# MCU.net
KiCad netlist of a schematic drawn in Altium Designer
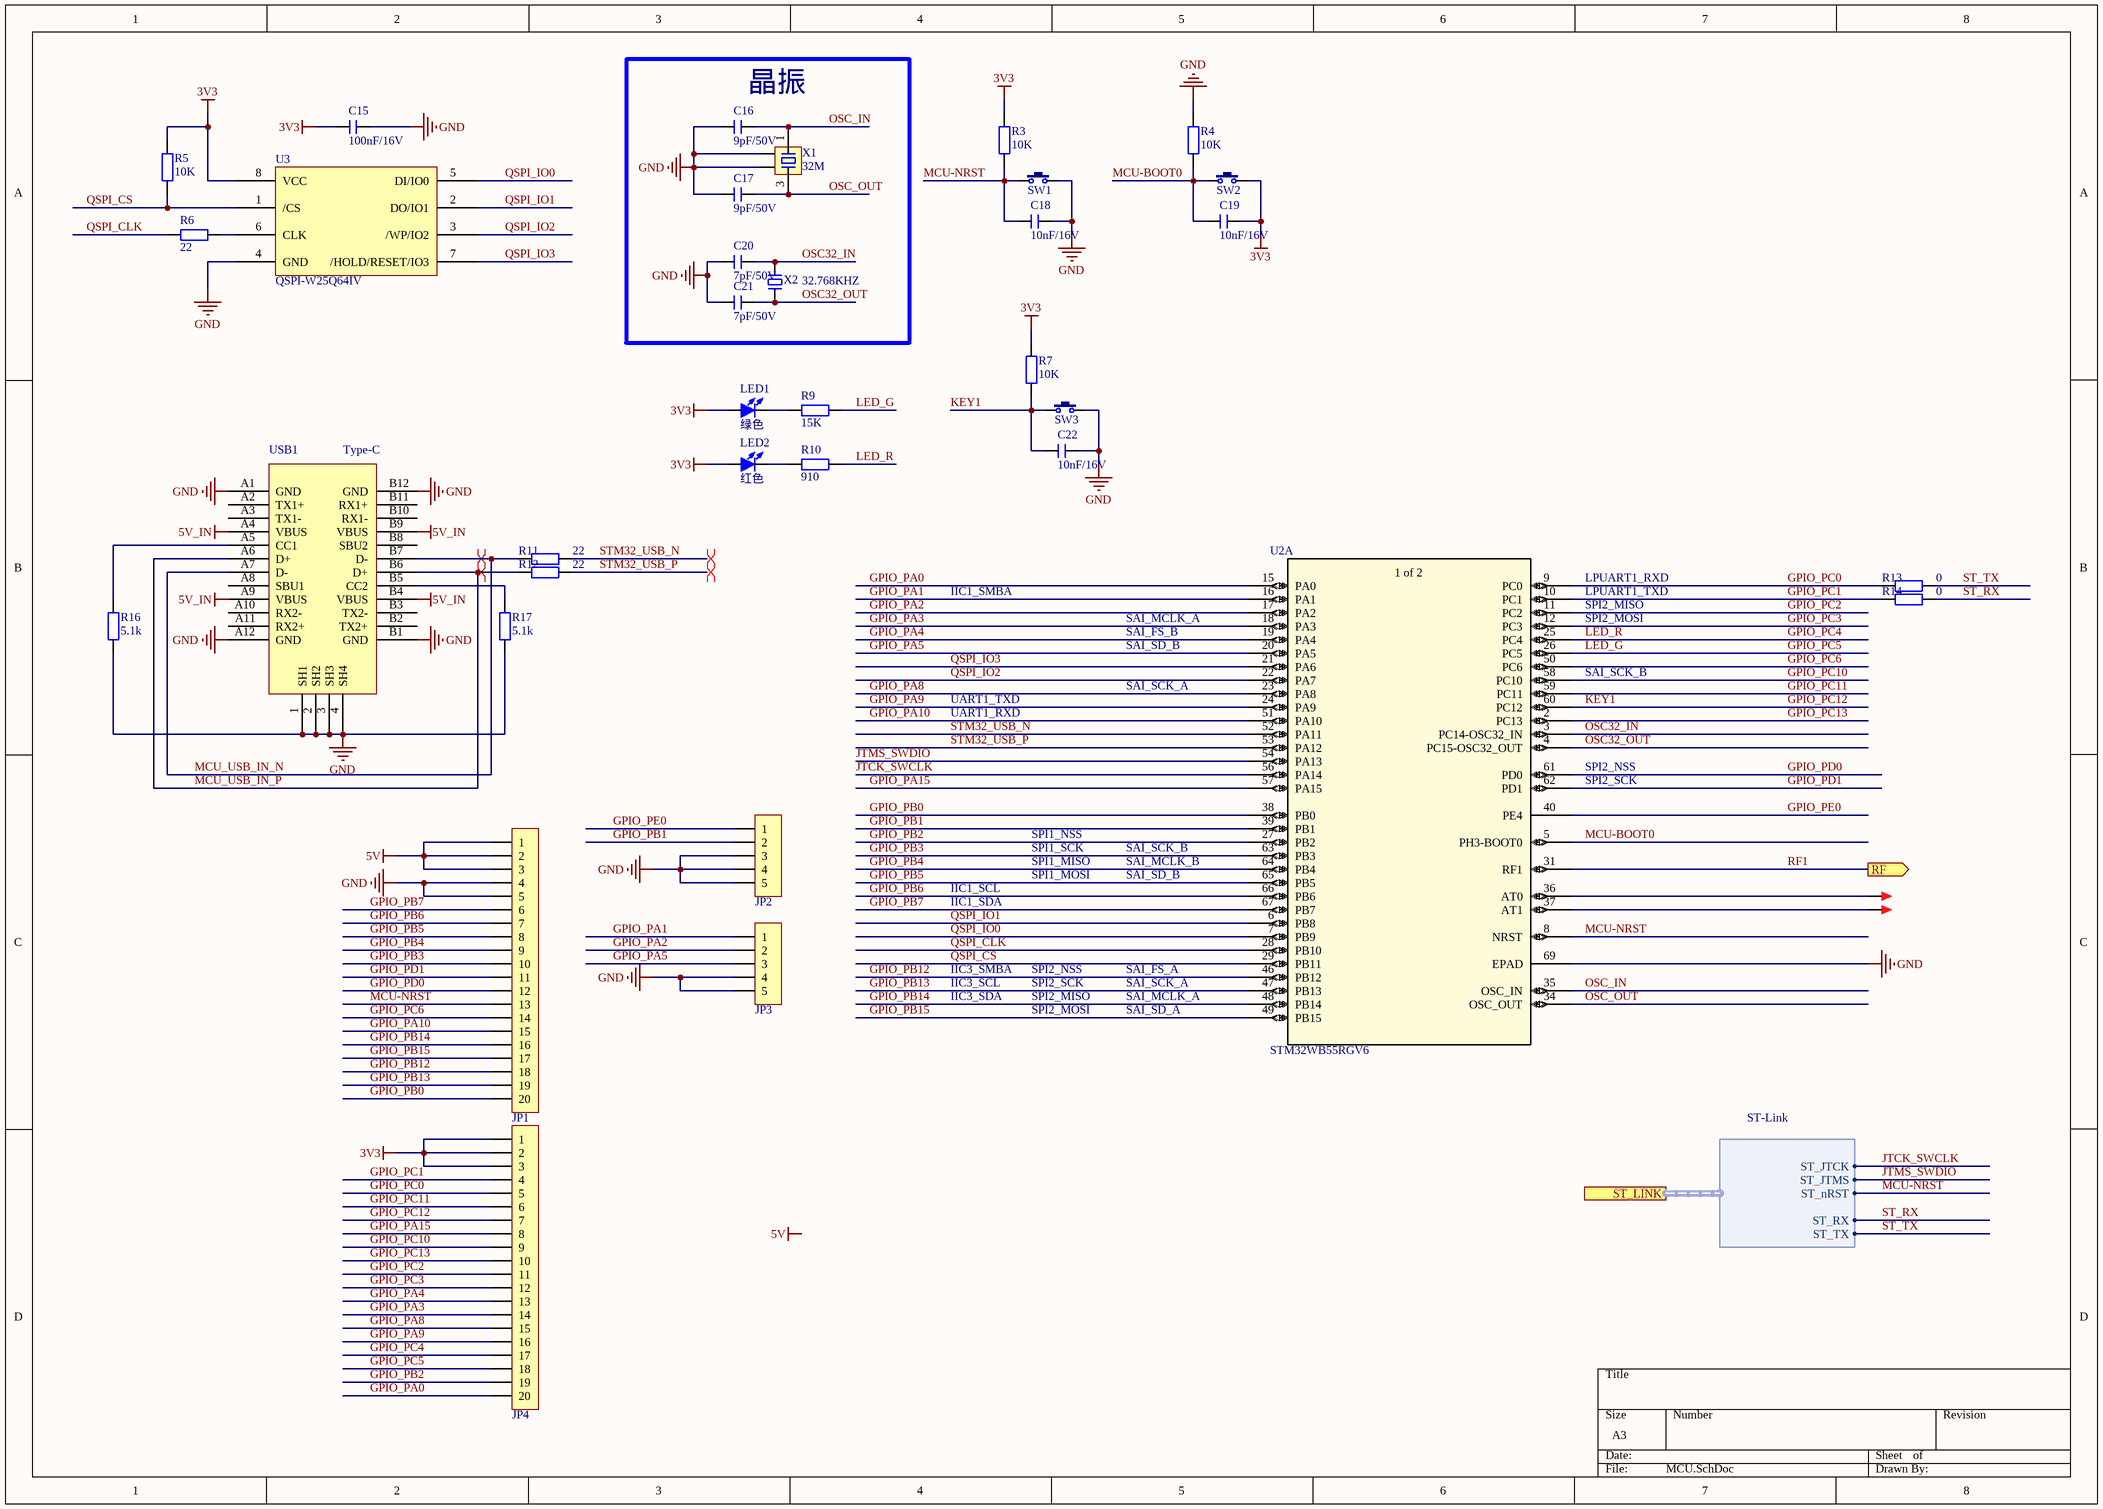
[diagram p0: MCU.SchDoc]

(export (version "E")
  (design (tool "Eeschema 10.0.6"))
  (components
    (comp (ref "C15")
      (value "100nF/16V")
      (footprint "C 0402_L")
      (description "贴片电容")
      (libsource (lib "3.1   - 电阻-电容-电感") (part "C"))
    )
    (comp (ref "C16")
      (value "9pF/50V")
      (footprint "C 0402_L")
      (description "贴片电容")
      (libsource (lib "3.1   - 电阻-电容-电感") (part "C"))
    )
    (comp (ref "C17")
      (value "9pF/50V")
      (footprint "C 0402_L")
      (description "贴片电容")
      (libsource (lib "3.1   - 电阻-电容-电感") (part "C"))
    )
    (comp (ref "C18")
      (value "10nF/16V")
      (footprint "C 0402_L")
      (description "贴片电容")
      (libsource (lib "3.1   - 电阻-电容-电感") (part "C"))
    )
    (comp (ref "C19")
      (value "10nF/16V")
      (footprint "C 0402_L")
      (description "贴片电容")
      (libsource (lib "3.1   - 电阻-电容-电感") (part "C"))
    )
    (comp (ref "C20")
      (value "7pF/50V")
      (footprint "C 0402_L")
      (description "贴片电容")
      (libsource (lib "3.1   - 电阻-电容-电感") (part "C"))
    )
    (comp (ref "C21")
      (value "7pF/50V")
      (footprint "C 0402_L")
      (description "贴片电容")
      (libsource (lib "3.1   - 电阻-电容-电感") (part "C"))
    )
    (comp (ref "C22")
      (value "10nF/16V")
      (footprint "C 0402_L")
      (description "贴片电容")
      (libsource (lib "3.1   - 电阻-电容-电感") (part "C"))
    )
    (comp (ref "JP1")
      (value "HDR-1X20")
      (footprint "HDR2.54-LI-20P")
      (description "20P接插件")
      (libsource (lib "4.5   - 接插件-脚距2.54") (part "Header 20"))
    )
    (comp (ref "JP2")
      (value "HDR-1X5")
      (footprint "HDR2.54-LI-5P")
      (description "5P接插件")
      (libsource (lib "4.5   - 接插件-脚距2.54") (part "Header 5"))
    )
    (comp (ref "JP3")
      (value "HDR-1X5")
      (footprint "HDR2.54-LI-5P")
      (description "5P接插件")
      (libsource (lib "4.5   - 接插件-脚距2.54") (part "Header 5"))
    )
    (comp (ref "JP4")
      (value "HDR-1X20")
      (footprint "HDR2.54-LI-20P")
      (description "20P接插件")
      (libsource (lib "4.5   - 接插件-脚距2.54") (part "Header 20"))
    )
    (comp (ref "LED1")
      (value "绿色")
      (footprint "LED")
      (description "C84267")
      (libsource (lib "9.1   - LED") (part "LED-SMD"))
    )
    (comp (ref "LED2")
      (value "红色")
      (footprint "LED")
      (description "C84267")
      (libsource (lib "9.1   - LED") (part "LED-SMD"))
    )
    (comp (ref "R3")
      (value "10K")
      (footprint "R 0402_L")
      (description "贴片电阻")
      (libsource (lib "3.1   - 电阻-电容-电感") (part "R"))
    )
    (comp (ref "R4")
      (value "10K")
      (footprint "R 0402_L")
      (description "贴片电阻")
      (libsource (lib "3.1   - 电阻-电容-电感") (part "R"))
    )
    (comp (ref "R5")
      (value "10K")
      (footprint "R 0402_L")
      (description "贴片电阻 0402 1%")
      (libsource (lib "3.1   - 电阻-电容-电感") (part "R"))
    )
    (comp (ref "R6")
      (value "22")
      (footprint "R 0402_L")
      (description "贴片电阻 0402 1%")
      (libsource (lib "3.1   - 电阻-电容-电感") (part "R"))
    )
    (comp (ref "R7")
      (value "10K")
      (footprint "R 0402_L")
      (description "贴片电阻")
      (libsource (lib "3.1   - 电阻-电容-电感") (part "R"))
    )
    (comp (ref "R9")
      (value "15K")
      (footprint "R 0402_L")
      (description "贴片电阻 0402 5%")
      (libsource (lib "3.1   - 电阻-电容-电感") (part "R"))
    )
    (comp (ref "R10")
      (value "910")
      (footprint "R 0402_L")
      (description "贴片电阻 0402 5%")
      (libsource (lib "3.1   - 电阻-电容-电感") (part "R"))
    )
    (comp (ref "R11")
      (value "22")
      (footprint "R 0402_L")
      (description "贴片电阻 0402 5%")
      (libsource (lib "3.1   - 电阻-电容-电感") (part "R"))
    )
    (comp (ref "R12")
      (value "22")
      (footprint "R 0402_L")
      (description "贴片电阻 0402 5%")
      (libsource (lib "3.1   - 电阻-电容-电感") (part "R"))
    )
    (comp (ref "R13")
      (value "0")
      (footprint "R 0402_L")
      (description "贴片电阻 0402 5%")
      (libsource (lib "3.1   - 电阻-电容-电感") (part "R"))
    )
    (comp (ref "R14")
      (value "0")
      (footprint "R 0402_L")
      (description "贴片电阻 0402 5%")
      (libsource (lib "3.1   - 电阻-电容-电感") (part "R"))
    )
    (comp (ref "R16")
      (value "5.1k")
      (footprint "R 0402_L")
      (description "贴片电阻 0402 5%")
      (libsource (lib "3.1   - 电阻-电容-电感") (part "R"))
    )
    (comp (ref "R17")
      (value "5.1k")
      (footprint "R 0402_L")
      (description "贴片电阻 0402 5%")
      (libsource (lib "3.1   - 电阻-电容-电感") (part "R"))
    )
    (comp (ref "SW1")
      (value "3x6x5")
      (footprint "按钮")
      (description "3x6轻触开关")
      (libsource (lib "5.1   - 按键-开关") (part "TSW 3x6"))
    )
    (comp (ref "SW2")
      (value "3x6x5")
      (footprint "按钮")
      (description "3x6轻触开关")
      (libsource (lib "5.1   - 按键-开关") (part "TSW 3x6"))
    )
    (comp (ref "SW3")
      (value "3x6x5")
      (footprint "按钮")
      (description "3x6轻触开关")
      (libsource (lib "5.1   - 按键-开关") (part "TSW 3x6"))
    )
    (comp (ref "TP1")
      (value "TEST")
      (footprint "TEST 1.2")
      (description "测试点")
      (libsource (lib "15.1 - 未分类器件") (part "TEST"))
    )
    (comp (ref "TP2")
      (value "TEST")
      (footprint "TEST 1.2")
      (description "测试点")
      (libsource (lib "15.1 - 未分类器件") (part "TEST"))
    )
    (comp (ref "U2")
      (value "STM32WB55RGV6")
      (footprint "VFQFN68-8x8mm-M")
      (description "No Description Available")
      (fields (field (name "COPYRIGHT") "Copyright (C) 2018 Accelerated Designs. All rights reserved"))
      (libsource (lib "2021-04-01_09-06-49") (part "STM32WB55RGV6"))
    )
    (comp (ref "U3")
      (value "QSPI-W25Q64IV")
      (footprint "QSPI")
      (libsource (lib "AltiumV15") (part "QSPI-W25Q256IV"))
    )
    (comp (ref "USB1")
      (value "Type-C")
      (footprint "Type-c接口")
      (libsource (lib "MyPcbLib") (part "USB-Type-C-TOP"))
    )
    (comp (ref "X1")
      (value "32M")
      (footprint "OSC 1612-4P")
      (description "4脚无源晶振")
      (libsource (lib "10.1 - 保险丝-晶振") (part "XTAL-4P"))
    )
    (comp (ref "X2")
      (value "32.768KHZ")
      (footprint "OSC 3215-2P")
      (description "2脚无源脚晶振")
      (libsource (lib "10.1 - 保险丝-晶振") (part "XTAL-2P"))
    )
  )
  (nets
    (net (code "2") (name "/GPIO_PA0") (class "Default")
      (node (ref "JP4") (pin "20") (pinfunction "20_20") (pintype "passive"))
      (node (ref "U2") (pin "15") (pinfunction "PA0_15") (pintype "bidirectional"))
    )
    (net (code "3") (name "/GPIO_PA1") (class "Default")
      (node (ref "JP3") (pin "1") (pinfunction "1_1") (pintype "passive"))
      (node (ref "U2") (pin "16") (pinfunction "PA1_16") (pintype "bidirectional"))
    )
    (net (code "4") (name "/GPIO_PA2") (class "Default")
      (node (ref "JP3") (pin "2") (pinfunction "2_2") (pintype "passive"))
      (node (ref "U2") (pin "17") (pinfunction "PA2_17") (pintype "bidirectional"))
    )
    (net (code "5") (name "/GPIO_PA3") (class "Default")
      (node (ref "JP4") (pin "14") (pinfunction "14_14") (pintype "passive"))
      (node (ref "U2") (pin "18") (pinfunction "PA3_18") (pintype "bidirectional"))
    )
    (net (code "6") (name "/GPIO_PA4") (class "Default")
      (node (ref "JP4") (pin "13") (pinfunction "13_13") (pintype "passive"))
      (node (ref "U2") (pin "19") (pinfunction "PA4_19") (pintype "bidirectional"))
    )
    (net (code "7") (name "/GPIO_PA5") (class "Default")
      (node (ref "JP3") (pin "3") (pinfunction "3_3") (pintype "passive"))
      (node (ref "U2") (pin "20") (pinfunction "PA5_20") (pintype "bidirectional"))
    )
    (net (code "8") (name "/GPIO_PA8") (class "Default")
      (node (ref "JP4") (pin "15") (pinfunction "15_15") (pintype "passive"))
      (node (ref "U2") (pin "23") (pinfunction "PA8_23") (pintype "bidirectional"))
    )
    (net (code "9") (name "/GPIO_PA9") (class "Default")
      (node (ref "JP4") (pin "16") (pinfunction "16_16") (pintype "passive"))
      (node (ref "U2") (pin "24") (pinfunction "PA9_24") (pintype "bidirectional"))
    )
    (net (code "10") (name "/GPIO_PA10") (class "Default")
      (node (ref "JP1") (pin "15") (pinfunction "15_15") (pintype "passive"))
      (node (ref "U2") (pin "51") (pinfunction "PA10_51") (pintype "bidirectional"))
    )
    (net (code "11") (name "/GPIO_PA15") (class "Default")
      (node (ref "JP4") (pin "8") (pinfunction "8_8") (pintype "passive"))
      (node (ref "U2") (pin "57") (pinfunction "PA15_57") (pintype "bidirectional"))
    )
    (net (code "12") (name "/GPIO_PB0") (class "Default")
      (node (ref "JP1") (pin "20") (pinfunction "20_20") (pintype "passive"))
      (node (ref "U2") (pin "38") (pinfunction "PB0_38") (pintype "bidirectional"))
    )
    (net (code "13") (name "/GPIO_PB1") (class "Default")
      (node (ref "JP2") (pin "2") (pinfunction "2_2") (pintype "passive"))
      (node (ref "U2") (pin "39") (pinfunction "PB1_39") (pintype "bidirectional"))
    )
    (net (code "14") (name "/GPIO_PB2") (class "Default")
      (node (ref "JP4") (pin "19") (pinfunction "19_19") (pintype "passive"))
      (node (ref "U2") (pin "27") (pinfunction "PB2_27") (pintype "bidirectional"))
    )
    (net (code "15") (name "/GPIO_PB3") (class "Default")
      (node (ref "JP1") (pin "10") (pinfunction "10_10") (pintype "passive"))
      (node (ref "U2") (pin "63") (pinfunction "PB3_63") (pintype "bidirectional"))
    )
    (net (code "16") (name "/GPIO_PB4") (class "Default")
      (node (ref "JP1") (pin "9") (pinfunction "9_9") (pintype "passive"))
      (node (ref "U2") (pin "64") (pinfunction "PB4_64") (pintype "bidirectional"))
    )
    (net (code "17") (name "/GPIO_PB5") (class "Default")
      (node (ref "JP1") (pin "8") (pinfunction "8_8") (pintype "passive"))
      (node (ref "U2") (pin "65") (pinfunction "PB5_65") (pintype "bidirectional"))
    )
    (net (code "18") (name "/GPIO_PB6") (class "Default")
      (node (ref "JP1") (pin "7") (pinfunction "7_7") (pintype "passive"))
      (node (ref "U2") (pin "66") (pinfunction "PB6_66") (pintype "bidirectional"))
    )
    (net (code "19") (name "/GPIO_PB7") (class "Default")
      (node (ref "JP1") (pin "6") (pinfunction "6_6") (pintype "passive"))
      (node (ref "U2") (pin "67") (pinfunction "PB7_67") (pintype "bidirectional"))
    )
    (net (code "20") (name "/GPIO_PB12") (class "Default")
      (node (ref "JP1") (pin "18") (pinfunction "18_18") (pintype "passive"))
      (node (ref "U2") (pin "46") (pinfunction "PB12_46") (pintype "bidirectional"))
    )
    (net (code "21") (name "/GPIO_PB13") (class "Default")
      (node (ref "JP1") (pin "19") (pinfunction "19_19") (pintype "passive"))
      (node (ref "U2") (pin "47") (pinfunction "PB13_47") (pintype "bidirectional"))
    )
    (net (code "22") (name "/GPIO_PB14") (class "Default")
      (node (ref "JP1") (pin "16") (pinfunction "16_16") (pintype "passive"))
      (node (ref "U2") (pin "48") (pinfunction "PB14_48") (pintype "bidirectional"))
    )
    (net (code "23") (name "/GPIO_PB15") (class "Default")
      (node (ref "JP1") (pin "17") (pinfunction "17_17") (pintype "passive"))
      (node (ref "U2") (pin "49") (pinfunction "PB15_49") (pintype "bidirectional"))
    )
    (net (code "24") (name "/GPIO_PC0") (class "Default")
      (node (ref "JP4") (pin "5") (pinfunction "5_5") (pintype "passive"))
      (node (ref "R13") (pin "2") (pinfunction "2_2") (pintype "passive"))
      (node (ref "U2") (pin "9") (pinfunction "PC0_9") (pintype "bidirectional"))
    )
    (net (code "25") (name "/GPIO_PC1") (class "Default")
      (node (ref "JP4") (pin "4") (pinfunction "4_4") (pintype "passive"))
      (node (ref "R14") (pin "2") (pinfunction "2_2") (pintype "passive"))
      (node (ref "U2") (pin "10") (pinfunction "PC1_10") (pintype "bidirectional"))
    )
    (net (code "26") (name "/GPIO_PC2") (class "Default")
      (node (ref "JP4") (pin "11") (pinfunction "11_11") (pintype "passive"))
      (node (ref "U2") (pin "11") (pinfunction "PC2_11") (pintype "bidirectional"))
    )
    (net (code "27") (name "/GPIO_PC3") (class "Default")
      (node (ref "JP4") (pin "12") (pinfunction "12_12") (pintype "passive"))
      (node (ref "U2") (pin "12") (pinfunction "PC3_12") (pintype "bidirectional"))
    )
    (net (code "28") (name "/GPIO_PC4") (class "Default")
      (node (ref "JP4") (pin "17") (pinfunction "17_17") (pintype "passive"))
      (node (ref "R10") (pin "1") (pinfunction "1_1") (pintype "passive"))
      (node (ref "U2") (pin "25") (pinfunction "PC4_25") (pintype "bidirectional"))
    )
    (net (code "29") (name "/GPIO_PC5") (class "Default")
      (node (ref "JP4") (pin "18") (pinfunction "18_18") (pintype "passive"))
      (node (ref "R9") (pin "1") (pinfunction "1_1") (pintype "passive"))
      (node (ref "U2") (pin "26") (pinfunction "PC5_26") (pintype "bidirectional"))
    )
    (net (code "30") (name "/GPIO_PC6") (class "Default")
      (node (ref "JP1") (pin "14") (pinfunction "14_14") (pintype "passive"))
      (node (ref "U2") (pin "50") (pinfunction "PC6_50") (pintype "bidirectional"))
    )
    (net (code "31") (name "/GPIO_PC10") (class "Default")
      (node (ref "JP4") (pin "9") (pinfunction "9_9") (pintype "passive"))
      (node (ref "U2") (pin "58") (pinfunction "PC10_58") (pintype "bidirectional"))
    )
    (net (code "32") (name "/GPIO_PC11") (class "Default")
      (node (ref "JP4") (pin "6") (pinfunction "6_6") (pintype "passive"))
      (node (ref "U2") (pin "59") (pinfunction "PC11_59") (pintype "bidirectional"))
    )
    (net (code "33") (name "/GPIO_PC12") (class "Default")
      (node (ref "C22") (pin "1") (pinfunction "1_1") (pintype "passive"))
      (node (ref "JP4") (pin "7") (pinfunction "7_7") (pintype "passive"))
      (node (ref "R7") (pin "1") (pinfunction "1_1") (pintype "passive"))
      (node (ref "SW3") (pin "1") (pinfunction "1_1") (pintype "passive"))
      (node (ref "U2") (pin "60") (pinfunction "PC12_60") (pintype "bidirectional"))
    )
    (net (code "34") (name "/GPIO_PC13") (class "Default")
      (node (ref "JP4") (pin "10") (pinfunction "10_10") (pintype "passive"))
      (node (ref "U2") (pin "2") (pinfunction "PC13_2") (pintype "bidirectional"))
    )
    (net (code "35") (name "/GPIO_PD0") (class "Default")
      (node (ref "JP1") (pin "12") (pinfunction "12_12") (pintype "passive"))
      (node (ref "U2") (pin "61") (pinfunction "PD0_61") (pintype "bidirectional"))
    )
    (net (code "36") (name "/GPIO_PD1") (class "Default")
      (node (ref "JP1") (pin "11") (pinfunction "11_11") (pintype "passive"))
      (node (ref "U2") (pin "62") (pinfunction "PD1_62") (pintype "bidirectional"))
    )
    (net (code "37") (name "/GPIO_PE0") (class "Default")
      (node (ref "JP2") (pin "1") (pinfunction "1_1") (pintype "passive"))
      (node (ref "U2") (pin "40") (pinfunction "PE4_40") (pintype "power_in"))
    )
    (net (code "38") (name "/JTCK_SWCLK") (class "Default")
      (node (ref "U2") (pin "56") (pinfunction "PA14_56") (pintype "bidirectional"))
    )
    (net (code "39") (name "/JTMS_SWDIO") (class "Default")
      (node (ref "U2") (pin "54") (pinfunction "PA13_54") (pintype "bidirectional"))
    )
    (net (code "40") (name "/MCU-BOOT0") (class "Default")
      (node (ref "C19") (pin "1") (pinfunction "1_1") (pintype "passive"))
      (node (ref "R4") (pin "1") (pinfunction "1_1") (pintype "passive"))
      (node (ref "SW2") (pin "1") (pinfunction "1_1") (pintype "passive"))
      (node (ref "U2") (pin "5") (pinfunction "PH3-BOOT0_5") (pintype "bidirectional"))
    )
    (net (code "41") (name "/MCU-NRST") (class "Default")
      (node (ref "C18") (pin "1") (pinfunction "1_1") (pintype "passive"))
      (node (ref "JP1") (pin "13") (pinfunction "13_13") (pintype "passive"))
      (node (ref "R3") (pin "1") (pinfunction "1_1") (pintype "passive"))
      (node (ref "SW1") (pin "1") (pinfunction "1_1") (pintype "passive"))
      (node (ref "U2") (pin "8") (pinfunction "NRST_8") (pintype "bidirectional"))
    )
    (net (code "42") (name "/MCU_USB_IN_N") (class "Default")
      (node (ref "R11") (pin "2") (pinfunction "2_2") (pintype "passive"))
      (node (ref "USB1") (pin "A7") (pinfunction "D-_A7") (pintype "passive"))
      (node (ref "USB1") (pin "B7") (pinfunction "D-_B7") (pintype "passive"))
    )
    (net (code "43") (name "/MCU_USB_IN_P") (class "Default")
      (node (ref "R12") (pin "2") (pinfunction "2_2") (pintype "passive"))
      (node (ref "USB1") (pin "A6") (pinfunction "D+_A6") (pintype "passive"))
      (node (ref "USB1") (pin "B6") (pinfunction "D+_B6") (pintype "passive"))
    )
    (net (code "44") (name "/OSC32_IN") (class "Default")
      (node (ref "C20") (pin "2") (pinfunction "2_2") (pintype "passive"))
      (node (ref "U2") (pin "3") (pinfunction "PC14-OSC32_IN_3") (pintype "bidirectional"))
      (node (ref "X2") (pin "2") (pinfunction "2_2") (pintype "passive"))
    )
    (net (code "45") (name "/OSC32_OUT") (class "Default")
      (node (ref "C21") (pin "2") (pinfunction "2_2") (pintype "passive"))
      (node (ref "U2") (pin "4") (pinfunction "PC15-OSC32_OUT_4") (pintype "bidirectional"))
      (node (ref "X2") (pin "1") (pinfunction "1_1") (pintype "passive"))
    )
    (net (code "46") (name "/OSC_IN") (class "Default")
      (node (ref "C16") (pin "2") (pinfunction "2_2") (pintype "passive"))
      (node (ref "U2") (pin "35") (pinfunction "OSC_IN_35") (pintype "bidirectional"))
      (node (ref "X1") (pin "1") (pinfunction "1_1") (pintype "passive"))
    )
    (net (code "47") (name "/OSC_OUT") (class "Default")
      (node (ref "C17") (pin "2") (pinfunction "2_2") (pintype "passive"))
      (node (ref "U2") (pin "34") (pinfunction "OSC_OUT_34") (pintype "bidirectional"))
      (node (ref "X1") (pin "3") (pinfunction "3_3") (pintype "passive"))
    )
    (net (code "48") (name "/QSPI_CLK") (class "Default")
      (node (ref "R6") (pin "1") (pinfunction "1_1") (pintype "passive"))
      (node (ref "U2") (pin "28") (pinfunction "PB10_28") (pintype "bidirectional"))
    )
    (net (code "49") (name "/QSPI_CS") (class "Default")
      (node (ref "R5") (pin "2") (pinfunction "2_2") (pintype "passive"))
      (node (ref "U2") (pin "29") (pinfunction "PB11_29") (pintype "bidirectional"))
      (node (ref "U3") (pin "1") (pinfunction "/CS_1") (pintype "passive"))
    )
    (net (code "50") (name "/QSPI_IO0") (class "Default")
      (node (ref "U2") (pin "7") (pinfunction "PB9_7") (pintype "bidirectional"))
      (node (ref "U3") (pin "5") (pinfunction "DI/IO0_5") (pintype "passive"))
    )
    (net (code "51") (name "/QSPI_IO1") (class "Default")
      (node (ref "U2") (pin "6") (pinfunction "PB8_6") (pintype "bidirectional"))
      (node (ref "U3") (pin "2") (pinfunction "DO/IO1_2") (pintype "passive"))
    )
    (net (code "52") (name "/QSPI_IO2") (class "Default")
      (node (ref "U2") (pin "22") (pinfunction "PA7_22") (pintype "bidirectional"))
      (node (ref "U3") (pin "3") (pinfunction "/WP/IO2_3") (pintype "passive"))
    )
    (net (code "53") (name "/QSPI_IO3") (class "Default")
      (node (ref "U2") (pin "21") (pinfunction "PA6_21") (pintype "bidirectional"))
      (node (ref "U3") (pin "7") (pinfunction "/HOLD/RESET/IO3_7") (pintype "passive"))
    )
    (net (code "54") (name "/RF1") (class "Default")
      (node (ref "U2") (pin "31") (pinfunction "RF1_31") (pintype "bidirectional"))
    )
    (net (code "55") (name "/STM32_USB_N") (class "Default")
      (node (ref "R11") (pin "1") (pinfunction "1_1") (pintype "passive"))
      (node (ref "U2") (pin "52") (pinfunction "PA11_52") (pintype "bidirectional"))
    )
    (net (code "56") (name "/STM32_USB_P") (class "Default")
      (node (ref "R12") (pin "1") (pinfunction "1_1") (pintype "passive"))
      (node (ref "U2") (pin "53") (pinfunction "PA12_53") (pintype "bidirectional"))
    )
    (net (code "57") (name "/ST_RX") (class "Default")
      (node (ref "R14") (pin "1") (pinfunction "1_1") (pintype "passive"))
    )
    (net (code "58") (name "/ST_TX") (class "Default")
      (node (ref "R13") (pin "1") (pinfunction "1_1") (pintype "passive"))
    )
    (net (code "60") (name "3V3") (class "Default")
      (node (ref "C15") (pin "2") (pinfunction "2_2") (pintype "passive"))
      (node (ref "C19") (pin "2") (pinfunction "2_2") (pintype "passive"))
      (node (ref "JP4") (pin "1") (pinfunction "1_1") (pintype "passive"))
      (node (ref "JP4") (pin "2") (pinfunction "2_2") (pintype "passive"))
      (node (ref "JP4") (pin "3") (pinfunction "3_3") (pintype "passive"))
      (node (ref "LED1") (pin "1") (pinfunction "A_1") (pintype "passive"))
      (node (ref "LED2") (pin "1") (pinfunction "A_1") (pintype "passive"))
      (node (ref "R3") (pin "2") (pinfunction "2_2") (pintype "passive"))
      (node (ref "R5") (pin "1") (pinfunction "1_1") (pintype "passive"))
      (node (ref "R7") (pin "2") (pinfunction "2_2") (pintype "passive"))
      (node (ref "SW2") (pin "2") (pinfunction "2_2") (pintype "passive"))
      (node (ref "U3") (pin "8") (pinfunction "VCC_8") (pintype "passive"))
    )
    (net (code "61") (name "5V") (class "Default")
      (node (ref "JP1") (pin "1") (pinfunction "1_1") (pintype "passive"))
      (node (ref "JP1") (pin "2") (pinfunction "2_2") (pintype "passive"))
      (node (ref "JP1") (pin "3") (pinfunction "3_3") (pintype "passive"))
    )
    (net (code "62") (name "5V_IN") (class "Default")
      (node (ref "USB1") (pin "A4") (pinfunction "VBUS_A4") (pintype "passive"))
      (node (ref "USB1") (pin "A9") (pinfunction "VBUS_A9") (pintype "passive"))
      (node (ref "USB1") (pin "B4") (pinfunction "VBUS_B4") (pintype "passive"))
      (node (ref "USB1") (pin "B9") (pinfunction "VBUS_B9") (pintype "passive"))
    )
    (net (code "63") (name "GND") (class "Default")
      (node (ref "C15") (pin "1") (pinfunction "1_1") (pintype "passive"))
      (node (ref "C16") (pin "1") (pinfunction "1_1") (pintype "passive"))
      (node (ref "C17") (pin "1") (pinfunction "1_1") (pintype "passive"))
      (node (ref "C18") (pin "2") (pinfunction "2_2") (pintype "passive"))
      (node (ref "C20") (pin "1") (pinfunction "1_1") (pintype "passive"))
      (node (ref "C21") (pin "1") (pinfunction "1_1") (pintype "passive"))
      (node (ref "C22") (pin "2") (pinfunction "2_2") (pintype "passive"))
      (node (ref "JP1") (pin "4") (pinfunction "4_4") (pintype "passive"))
      (node (ref "JP1") (pin "5") (pinfunction "5_5") (pintype "passive"))
      (node (ref "JP2") (pin "3") (pinfunction "3_3") (pintype "passive"))
      (node (ref "JP2") (pin "4") (pinfunction "4_4") (pintype "passive"))
      (node (ref "JP2") (pin "5") (pinfunction "5_5") (pintype "passive"))
      (node (ref "JP3") (pin "4") (pinfunction "4_4") (pintype "passive"))
      (node (ref "JP3") (pin "5") (pinfunction "5_5") (pintype "passive"))
      (node (ref "R16") (pin "2") (pinfunction "2_2") (pintype "passive"))
      (node (ref "R17") (pin "2") (pinfunction "2_2") (pintype "passive"))
      (node (ref "R4") (pin "2") (pinfunction "2_2") (pintype "passive"))
      (node (ref "SW1") (pin "2") (pinfunction "2_2") (pintype "passive"))
      (node (ref "SW3") (pin "2") (pinfunction "2_2") (pintype "passive"))
      (node (ref "U2") (pin "69") (pinfunction "EPAD_69") (pintype "passive"))
      (node (ref "U3") (pin "4") (pinfunction "GND_4") (pintype "passive"))
      (node (ref "USB1") (pin "1") (pinfunction "SH1_1") (pintype "passive"))
      (node (ref "USB1") (pin "2") (pinfunction "SH2_2") (pintype "passive"))
      (node (ref "USB1") (pin "3") (pinfunction "SH3_3") (pintype "passive"))
      (node (ref "USB1") (pin "4") (pinfunction "SH4_4") (pintype "passive"))
      (node (ref "USB1") (pin "A1") (pinfunction "GND_A1") (pintype "passive"))
      (node (ref "USB1") (pin "A12") (pinfunction "GND_A12") (pintype "passive"))
      (node (ref "USB1") (pin "B1") (pinfunction "GND_B1") (pintype "passive"))
      (node (ref "USB1") (pin "B12") (pinfunction "GND_B12") (pintype "passive"))
      (node (ref "X1") (pin "2") (pinfunction "2_2") (pintype "passive"))
      (node (ref "X1") (pin "4") (pinfunction "4_4") (pintype "passive"))
    )
    (net (code "64") (name "Net-(LED1-K)") (class "Default")
      (node (ref "LED1") (pin "2") (pinfunction "K_2") (pintype "passive"))
      (node (ref "R9") (pin "2") (pinfunction "2_2") (pintype "passive"))
    )
    (net (code "65") (name "Net-(LED2-K)") (class "Default")
      (node (ref "LED2") (pin "2") (pinfunction "K_2") (pintype "passive"))
      (node (ref "R10") (pin "2") (pinfunction "2_2") (pintype "passive"))
    )
    (net (code "66") (name "Net-(U2A-AT0)") (class "Default")
      (node (ref "TP1") (pin "1") (pinfunction "1_1") (pintype "passive"))
      (node (ref "U2") (pin "36") (pinfunction "AT0_36") (pintype "bidirectional"))
    )
    (net (code "67") (name "Net-(U2A-AT1)") (class "Default")
      (node (ref "TP2") (pin "1") (pinfunction "1_1") (pintype "passive"))
      (node (ref "U2") (pin "37") (pinfunction "AT1_37") (pintype "bidirectional"))
    )
    (net (code "68") (name "Net-(U3-CLK)") (class "Default")
      (node (ref "R6") (pin "2") (pinfunction "2_2") (pintype "passive"))
      (node (ref "U3") (pin "6") (pinfunction "CLK_6") (pintype "passive"))
    )
    (net (code "69") (name "Net-(USB1-CC1)") (class "Default")
      (node (ref "R16") (pin "1") (pinfunction "1_1") (pintype "passive"))
      (node (ref "USB1") (pin "A5") (pinfunction "CC1_A5") (pintype "passive"))
    )
    (net (code "70") (name "Net-(USB1-CC2)") (class "Default")
      (node (ref "R17") (pin "1") (pinfunction "1_1") (pintype "passive"))
      (node (ref "USB1") (pin "B5") (pinfunction "CC2_B5") (pintype "passive"))
    )
    (net (code "71") (name "unconnected-(USB1-RX1+-PadB11)") (class "Default")
      (node (ref "USB1") (pin "B11") (pinfunction "RX1+_B11") (pintype "passive"))
    )
    (net (code "72") (name "unconnected-(USB1-RX1--PadB10)") (class "Default")
      (node (ref "USB1") (pin "B10") (pinfunction "RX1-_B10") (pintype "passive"))
    )
    (net (code "73") (name "unconnected-(USB1-RX2+-PadA11)") (class "Default")
      (node (ref "USB1") (pin "A11") (pinfunction "RX2+_A11") (pintype "passive"))
    )
    (net (code "74") (name "unconnected-(USB1-RX2--PadA10)") (class "Default")
      (node (ref "USB1") (pin "A10") (pinfunction "RX2-_A10") (pintype "passive"))
    )
    (net (code "75") (name "unconnected-(USB1-SBU1-PadA8)") (class "Default")
      (node (ref "USB1") (pin "A8") (pinfunction "SBU1_A8") (pintype "passive"))
    )
    (net (code "76") (name "unconnected-(USB1-SBU2-PadB8)") (class "Default")
      (node (ref "USB1") (pin "B8") (pinfunction "SBU2_B8") (pintype "passive"))
    )
    (net (code "77") (name "unconnected-(USB1-TX1+-PadA2)") (class "Default")
      (node (ref "USB1") (pin "A2") (pinfunction "TX1+_A2") (pintype "passive"))
    )
    (net (code "78") (name "unconnected-(USB1-TX1--PadA3)") (class "Default")
      (node (ref "USB1") (pin "A3") (pinfunction "TX1-_A3") (pintype "passive"))
    )
    (net (code "79") (name "unconnected-(USB1-TX2+-PadB2)") (class "Default")
      (node (ref "USB1") (pin "B2") (pinfunction "TX2+_B2") (pintype "passive"))
    )
    (net (code "80") (name "unconnected-(USB1-TX2--PadB3)") (class "Default")
      (node (ref "USB1") (pin "B3") (pinfunction "TX2-_B3") (pintype "passive"))
    )
  )
)
